# Alarm_system.net
KiCad netlist of a schematic drawn in Altium Designer
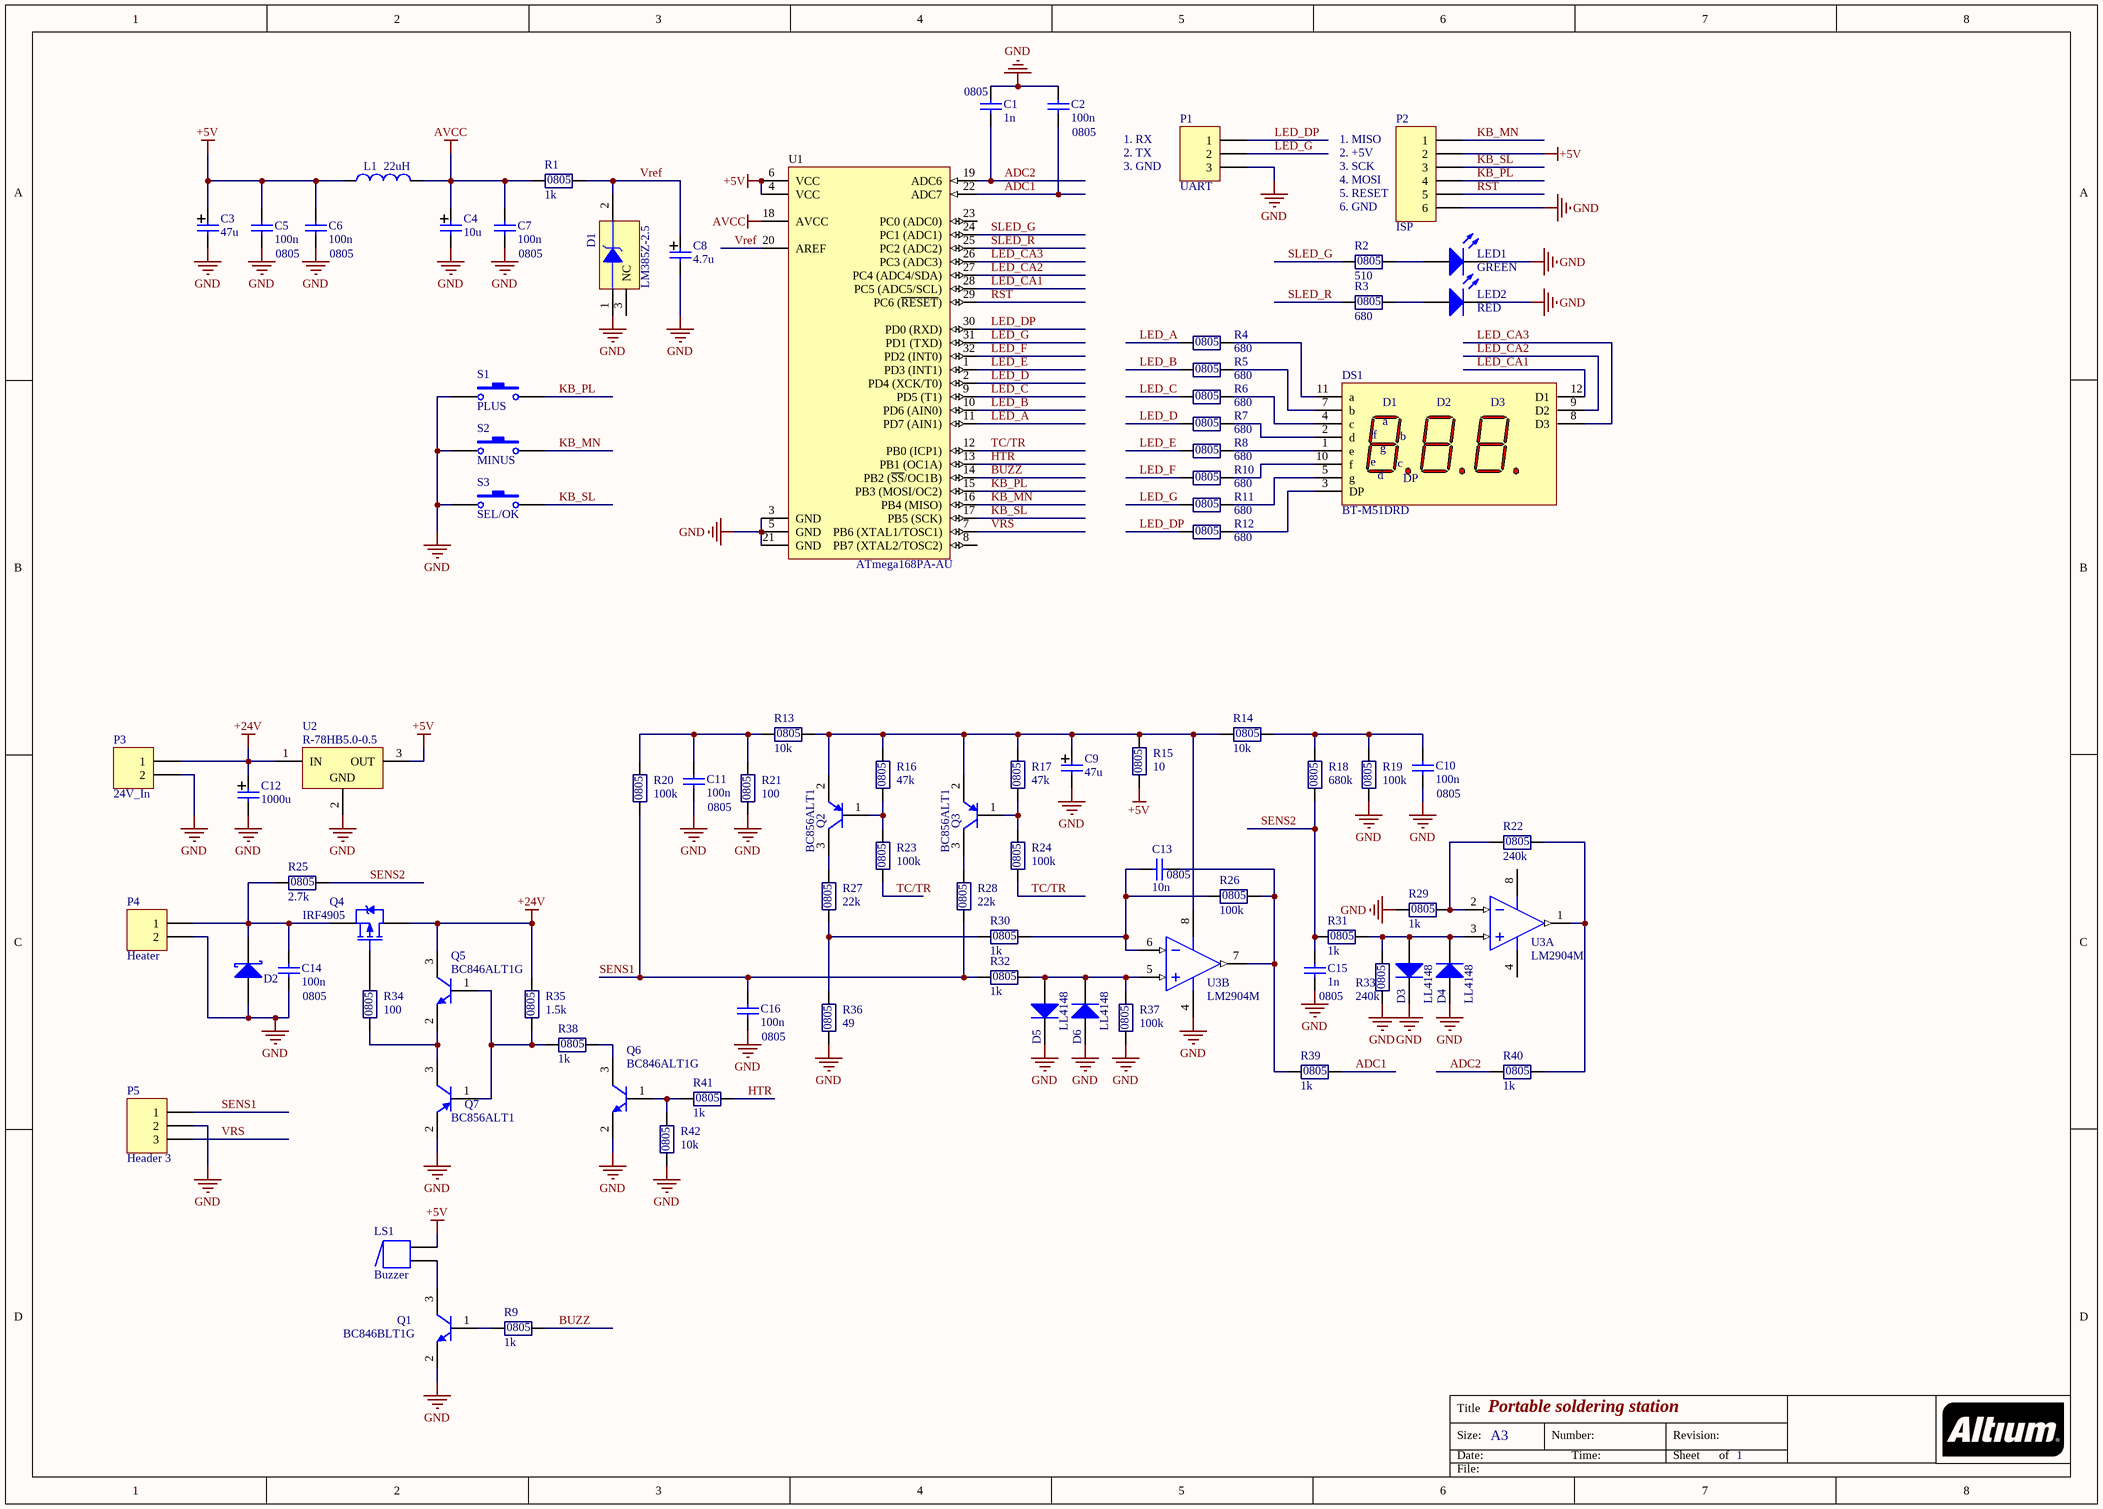
[diagram p0: Alarm system.SchDoc]

(export (version "E")
  (design (tool "Eeschema 10.0.6"))
  (components
    (comp (ref "C1")
      (value "0805")
      (footprint "CAPC2012X110N")
      (fields (field (name "ALTIUM_VALUE") "1n"))
      (libsource (lib "Passive components") (part "CAP"))
    )
    (comp (ref "C2")
      (value "0805")
      (footprint "CAPC2012X110N")
      (fields (field (name "ALTIUM_VALUE") "100n"))
      (libsource (lib "Passive components") (part "CAP"))
    )
    (comp (ref "C3")
      (value "47u")
      (footprint "CAPPR250-500X1100")
      (fields (field (name "Comment") "CAP_POL"))
      (libsource (lib "Passive components") (part "CAP_POL"))
    )
    (comp (ref "C4")
      (value "10u")
      (footprint "CAPPR250-500X1100")
      (fields (field (name "Comment") "CAP_POL"))
      (libsource (lib "Passive components") (part "CAP_POL"))
    )
    (comp (ref "C5")
      (value "0805")
      (footprint "CAPC2012X110N")
      (fields (field (name "ALTIUM_VALUE") "100n"))
      (libsource (lib "Passive components") (part "CAP"))
    )
    (comp (ref "C6")
      (value "0805")
      (footprint "CAPC2012X110N")
      (fields (field (name "ALTIUM_VALUE") "100n"))
      (libsource (lib "Passive components") (part "CAP"))
    )
    (comp (ref "C7")
      (value "0805")
      (footprint "CAPC2012X110N")
      (fields (field (name "ALTIUM_VALUE") "100n"))
      (libsource (lib "Passive components") (part "CAP"))
    )
    (comp (ref "C8")
      (value "4.7u")
      (footprint "CAPPR250-500X1100")
      (fields (field (name "Comment") "CAP_POL"))
      (libsource (lib "Passive components") (part "CAP_POL"))
    )
    (comp (ref "C9")
      (value "47u")
      (footprint "CAPPR250-500X1100")
      (fields (field (name "Comment") "CAP_POL"))
      (libsource (lib "Passive components") (part "CAP_POL"))
    )
    (comp (ref "C10")
      (value "0805")
      (footprint "CAPC2012X110N")
      (fields (field (name "ALTIUM_VALUE") "100n"))
      (libsource (lib "Passive components") (part "CAP"))
    )
    (comp (ref "C11")
      (value "0805")
      (footprint "CAPC2012X110N")
      (fields (field (name "ALTIUM_VALUE") "100n"))
      (libsource (lib "Passive components") (part "CAP"))
    )
    (comp (ref "C12")
      (value "1000u")
      (footprint "CAPPR500-1300X2150")
      (fields (field (name "Comment") "CAP_POL"))
      (libsource (lib "Passive components") (part "CAP_POL"))
    )
    (comp (ref "C13")
      (value "0805")
      (footprint "CAPC2012X110N")
      (fields (field (name "ALTIUM_VALUE") "10n"))
      (libsource (lib "Passive components") (part "CAP"))
    )
    (comp (ref "C14")
      (value "0805")
      (footprint "CAPC2012X110N")
      (fields (field (name "ALTIUM_VALUE") "100n"))
      (libsource (lib "Passive components") (part "CAP"))
    )
    (comp (ref "C15")
      (value "0805")
      (footprint "CAPC2012X110N")
      (fields (field (name "ALTIUM_VALUE") "1n"))
      (libsource (lib "Passive components") (part "CAP"))
    )
    (comp (ref "C16")
      (value "0805")
      (footprint "CAPC2012X110N")
      (fields (field (name "ALTIUM_VALUE") "100n"))
      (libsource (lib "Passive components") (part "CAP"))
    )
    (comp (ref "D1")
      (value "LM385Z-2.5")
      (footprint "TO-92AA-P127")
      (description "Micropower Voltage Reference Diode")
      (fields (field (name "PUBLISHER") "Altium Limited"))
      (libsource (lib "Motorola Power Mgt Voltage Reference") (part "LM385Z-2.5"))
    )
    (comp (ref "D2")
      (value "Schottky")
      (footprint "DO-41")
      (description "Schottky Rectifier")
      (libsource (lib "Diodes - Bridge Rectifiers") (part "Schottky"))
    )
    (comp (ref "D3")
      (value "LL4148")
      (footprint "SOD80")
      (description "Diode")
      (libsource (lib "Diodes - Bridge Rectifiers") (part "Diode"))
    )
    (comp (ref "D4")
      (value "LL4148")
      (footprint "SOD80")
      (description "Diode")
      (libsource (lib "Diodes - Bridge Rectifiers") (part "Diode"))
    )
    (comp (ref "D5")
      (value "LL4148")
      (footprint "SOD80")
      (description "Diode")
      (libsource (lib "Diodes - Bridge Rectifiers") (part "Diode"))
    )
    (comp (ref "D6")
      (value "LL4148")
      (footprint "SOD80")
      (description "Diode")
      (libsource (lib "Diodes - Bridge Rectifiers") (part "Diode"))
    )
    (comp (ref "DS1")
      (value "BT-M51DRD")
      (footprint "BT-M51DRD")
      (libsource (lib "Indicators") (part "Led_Ind_3_Digit"))
    )
    (comp (ref "L1")
      (value "22uH")
      (footprint "IND_BOURNS_PM43")
      (libsource (lib "ss3x7enc") (part "Drossel_AX"))
    )
    (comp (ref "LED1")
      (value "GREEN")
      (footprint "LED_3MM_GREEN_1C-2A")
      (description "Typical INFRARED GaAs LED")
      (fields (field (name "PUBLISHER") "Altium Limited"))
      (libsource (lib "Miscellaneous Devices") (part "LED0"))
    )
    (comp (ref "LED2")
      (value "RED")
      (footprint "LED_3MM_RED_1C-2A")
      (description "Typical INFRARED GaAs LED")
      (fields (field (name "PUBLISHER") "Altium Limited"))
      (libsource (lib "Miscellaneous Devices") (part "LED0"))
    )
    (comp (ref "LS1")
      (value "Buzzer")
      (footprint "buzzer")
      (description "Magnetic Transducer Buzzer")
      (fields (field (name "PUBLISHER") "Altium Limited"))
      (libsource (lib "Miscellaneous Devices") (part "Buzzer"))
    )
    (comp (ref "P1")
      (value "UART")
      (footprint "961103-6404-AR")
      (description "Header, 3-Pin")
      (fields (field (name "PUBLISHER") "Altium Limited"))
      (libsource (lib "Miscellaneous Connectors") (part "Header 3"))
    )
    (comp (ref "P2")
      (value "ISP")
      (footprint "961106-6404-AR")
      (description "Header, 6-Pin")
      (fields (field (name "PUBLISHER") "Altium Limited"))
      (libsource (lib "Miscellaneous Connectors") (part "Header 6"))
    )
    (comp (ref "P3")
      (value "24V_In")
      (footprint "PHOENIX_1715721")
      (description "Header, 2-Pin")
      (fields (field (name "PUBLISHER") "Altium Limited"))
      (libsource (lib "Miscellaneous Connectors") (part "Header 2"))
    )
    (comp (ref "P4")
      (value "Heater")
      (footprint "PHOENIX_1715721")
      (description "Header, 2-Pin")
      (fields (field (name "PUBLISHER") "Altium Limited"))
      (libsource (lib "Miscellaneous Connectors") (part "Header 2"))
    )
    (comp (ref "P5")
      (value "Header 3")
      (footprint "961103-6404-AR")
      (description "Header, 3-Pin")
      (fields (field (name "PUBLISHER") "Altium Limited"))
      (libsource (lib "Miscellaneous Connectors") (part "Header 3"))
    )
    (comp (ref "Q1")
      (value "BC846BLT1G")
      (footprint "SOT95P230X110-3N")
      (description "General Purpose Transistor, NPN Silicon, 3-Pin SOT-23, Pb-Free, Tape and Reel")
      (fields (field (name "MANUFACTURER") "On Semiconductor"))
      (libsource (lib "ON Semi General Purpose Transistors") (part "BC846BLT1G"))
    )
    (comp (ref "Q2")
      (value "BC856ALT1")
      (footprint "SOT95P230X110-3N")
      (description "General Purpose Transistor, PNP Silicon, 3-Pin SOT-23, Tape and Reel")
      (fields (field (name "MANUFACTURER") "On Semiconductor"))
      (libsource (lib "ON Semi General Purpose Transistors") (part "BC856ALT1"))
    )
    (comp (ref "Q3")
      (value "BC856ALT1")
      (footprint "SOT95P230X110-3N")
      (description "General Purpose Transistor, PNP Silicon, 3-Pin SOT-23, Tape and Reel")
      (fields (field (name "MANUFACTURER") "On Semiconductor"))
      (libsource (lib "ON Semi General Purpose Transistors") (part "BC856ALT1"))
    )
    (comp (ref "Q4")
      (value "IRF4905")
      (footprint "TO-220AB")
      (description "HEXFET Power MOSFET")
      (fields (field (name "PUBLISHER") "Altium Limited"))
      (libsource (lib "IR Discrete MOSFET - Power") (part "IRF4905"))
    )
    (comp (ref "Q5")
      (value "BC846ALT1G")
      (footprint "SOT95P230X110-3N")
      (description "General Purpose Transistor, NPN Silicon, 3-Pin SOT-23, Pb-Free, Tape and Reel")
      (fields (field (name "MANUFACTURER") "On Semiconductor"))
      (libsource (lib "ON Semi General Purpose Transistors") (part "BC846ALT1G"))
    )
    (comp (ref "Q6")
      (value "BC846ALT1G")
      (footprint "SOT95P230X110-3N")
      (description "General Purpose Transistor, NPN Silicon, 3-Pin SOT-23, Pb-Free, Tape and Reel")
      (fields (field (name "MANUFACTURER") "On Semiconductor"))
      (libsource (lib "ON Semi General Purpose Transistors") (part "BC846ALT1G"))
    )
    (comp (ref "Q7")
      (value "BC856ALT1")
      (footprint "SOT95P230X110-3N")
      (description "General Purpose Transistor, PNP Silicon, 3-Pin SOT-23, Tape and Reel")
      (fields (field (name "MANUFACTURER") "On Semiconductor"))
      (libsource (lib "ON Semi General Purpose Transistors") (part "BC856ALT1"))
    )
    (comp (ref "R1")
      (value "0805")
      (footprint "RESC2012X50N")
      (fields (field (name "ALTIUM_VALUE") "1k"))
      (libsource (lib "Passive components") (part "Resistor"))
    )
    (comp (ref "R2")
      (value "0805")
      (footprint "RESC2012X50N")
      (fields (field (name "ALTIUM_VALUE") "510"))
      (libsource (lib "Passive components") (part "Resistor"))
    )
    (comp (ref "R3")
      (value "0805")
      (footprint "RESC2012X50N")
      (fields (field (name "ALTIUM_VALUE") "680"))
      (libsource (lib "Passive components") (part "Resistor"))
    )
    (comp (ref "R4")
      (value "0805")
      (footprint "RESC2012X50N")
      (fields (field (name "ALTIUM_VALUE") "680"))
      (libsource (lib "Passive components") (part "Resistor"))
    )
    (comp (ref "R5")
      (value "0805")
      (footprint "RESC2012X50N")
      (fields (field (name "ALTIUM_VALUE") "680"))
      (libsource (lib "Passive components") (part "Resistor"))
    )
    (comp (ref "R6")
      (value "0805")
      (footprint "RESC2012X50N")
      (fields (field (name "ALTIUM_VALUE") "680"))
      (libsource (lib "Passive components") (part "Resistor"))
    )
    (comp (ref "R7")
      (value "0805")
      (footprint "RESC2012X50N")
      (fields (field (name "ALTIUM_VALUE") "680"))
      (libsource (lib "Passive components") (part "Resistor"))
    )
    (comp (ref "R8")
      (value "0805")
      (footprint "RESC2012X50N")
      (fields (field (name "ALTIUM_VALUE") "680"))
      (libsource (lib "Passive components") (part "Resistor"))
    )
    (comp (ref "R9")
      (value "0805")
      (footprint "RESC2012X50N")
      (fields (field (name "ALTIUM_VALUE") "1k"))
      (libsource (lib "Passive components") (part "Resistor"))
    )
    (comp (ref "R10")
      (value "0805")
      (footprint "RESC2012X50N")
      (fields (field (name "ALTIUM_VALUE") "680"))
      (libsource (lib "Passive components") (part "Resistor"))
    )
    (comp (ref "R11")
      (value "0805")
      (footprint "RESC2012X50N")
      (fields (field (name "ALTIUM_VALUE") "680"))
      (libsource (lib "Passive components") (part "Resistor"))
    )
    (comp (ref "R12")
      (value "0805")
      (footprint "RESC2012X50N")
      (fields (field (name "ALTIUM_VALUE") "680"))
      (libsource (lib "Passive components") (part "Resistor"))
    )
    (comp (ref "R13")
      (value "0805")
      (footprint "RESC2012X50N")
      (fields (field (name "ALTIUM_VALUE") "10k"))
      (libsource (lib "Passive components") (part "Resistor"))
    )
    (comp (ref "R14")
      (value "0805")
      (footprint "RESC2012X50N")
      (fields (field (name "ALTIUM_VALUE") "10k"))
      (libsource (lib "Passive components") (part "Resistor"))
    )
    (comp (ref "R15")
      (value "0805")
      (footprint "RESC2012X50N")
      (fields (field (name "ALTIUM_VALUE") "10"))
      (libsource (lib "Passive components") (part "Resistor"))
    )
    (comp (ref "R16")
      (value "0805")
      (footprint "RESC2012X50N")
      (fields (field (name "ALTIUM_VALUE") "47k"))
      (libsource (lib "Passive components") (part "Resistor"))
    )
    (comp (ref "R17")
      (value "0805")
      (footprint "RESC2012X50N")
      (fields (field (name "ALTIUM_VALUE") "47k"))
      (libsource (lib "Passive components") (part "Resistor"))
    )
    (comp (ref "R18")
      (value "0805")
      (footprint "RESC2012X50N")
      (fields (field (name "ALTIUM_VALUE") "680k"))
      (libsource (lib "Passive components") (part "Resistor"))
    )
    (comp (ref "R19")
      (value "0805")
      (footprint "RESC2012X50N")
      (fields (field (name "ALTIUM_VALUE") "100k"))
      (libsource (lib "Passive components") (part "Resistor"))
    )
    (comp (ref "R20")
      (value "0805")
      (footprint "RESC2012X50N")
      (fields (field (name "ALTIUM_VALUE") "100k"))
      (libsource (lib "Passive components") (part "Resistor"))
    )
    (comp (ref "R21")
      (value "0805")
      (footprint "RESC2012X50N")
      (fields (field (name "ALTIUM_VALUE") "100"))
      (libsource (lib "Passive components") (part "Resistor"))
    )
    (comp (ref "R22")
      (value "0805")
      (footprint "RESC2012X50N")
      (fields (field (name "ALTIUM_VALUE") "240k"))
      (libsource (lib "Passive components") (part "Resistor"))
    )
    (comp (ref "R23")
      (value "0805")
      (footprint "RESC2012X50N")
      (fields (field (name "ALTIUM_VALUE") "100k"))
      (libsource (lib "Passive components") (part "Resistor"))
    )
    (comp (ref "R24")
      (value "0805")
      (footprint "RESC2012X50N")
      (fields (field (name "ALTIUM_VALUE") "100k"))
      (libsource (lib "Passive components") (part "Resistor"))
    )
    (comp (ref "R25")
      (value "0805")
      (footprint "RESC2012X50N")
      (fields (field (name "ALTIUM_VALUE") "2.7k"))
      (libsource (lib "Passive components") (part "Resistor"))
    )
    (comp (ref "R26")
      (value "0805")
      (footprint "RESC2012X50N")
      (fields (field (name "ALTIUM_VALUE") "100k"))
      (libsource (lib "Passive components") (part "Resistor"))
    )
    (comp (ref "R27")
      (value "0805")
      (footprint "RESC2012X50N")
      (fields (field (name "ALTIUM_VALUE") "22k"))
      (libsource (lib "Passive components") (part "Resistor"))
    )
    (comp (ref "R28")
      (value "0805")
      (footprint "RESC2012X50N")
      (fields (field (name "ALTIUM_VALUE") "22k"))
      (libsource (lib "Passive components") (part "Resistor"))
    )
    (comp (ref "R29")
      (value "0805")
      (footprint "RESC2012X50N")
      (fields (field (name "ALTIUM_VALUE") "1k"))
      (libsource (lib "Passive components") (part "Resistor"))
    )
    (comp (ref "R30")
      (value "0805")
      (footprint "RESC2012X50N")
      (fields (field (name "ALTIUM_VALUE") "1k"))
      (libsource (lib "Passive components") (part "Resistor"))
    )
    (comp (ref "R31")
      (value "0805")
      (footprint "RESC2012X50N")
      (fields (field (name "ALTIUM_VALUE") "1k"))
      (libsource (lib "Passive components") (part "Resistor"))
    )
    (comp (ref "R32")
      (value "0805")
      (footprint "RESC2012X50N")
      (fields (field (name "ALTIUM_VALUE") "1k"))
      (libsource (lib "Passive components") (part "Resistor"))
    )
    (comp (ref "R33")
      (value "0805")
      (footprint "RESC2012X50N")
      (fields (field (name "ALTIUM_VALUE") "240k"))
      (libsource (lib "Passive components") (part "Resistor"))
    )
    (comp (ref "R34")
      (value "0805")
      (footprint "RESC2012X50N")
      (fields (field (name "ALTIUM_VALUE") "100"))
      (libsource (lib "Passive components") (part "Resistor"))
    )
    (comp (ref "R35")
      (value "0805")
      (footprint "RESC2012X50N")
      (fields (field (name "ALTIUM_VALUE") "1.5k"))
      (libsource (lib "Passive components") (part "Resistor"))
    )
    (comp (ref "R36")
      (value "0805")
      (footprint "RESC2012X50N")
      (fields (field (name "ALTIUM_VALUE") "49"))
      (libsource (lib "Passive components") (part "Resistor"))
    )
    (comp (ref "R37")
      (value "0805")
      (footprint "RESC2012X50N")
      (fields (field (name "ALTIUM_VALUE") "100k"))
      (libsource (lib "Passive components") (part "Resistor"))
    )
    (comp (ref "R38")
      (value "0805")
      (footprint "RESC2012X50N")
      (fields (field (name "ALTIUM_VALUE") "1k"))
      (libsource (lib "Passive components") (part "Resistor"))
    )
    (comp (ref "R39")
      (value "0805")
      (footprint "RESC2012X50N")
      (fields (field (name "ALTIUM_VALUE") "1k"))
      (libsource (lib "Passive components") (part "Resistor"))
    )
    (comp (ref "R40")
      (value "0805")
      (footprint "RESC2012X50N")
      (fields (field (name "ALTIUM_VALUE") "1k"))
      (libsource (lib "Passive components") (part "Resistor"))
    )
    (comp (ref "R41")
      (value "0805")
      (footprint "RESC2012X50N")
      (fields (field (name "ALTIUM_VALUE") "1k"))
      (libsource (lib "Passive components") (part "Resistor"))
    )
    (comp (ref "R42")
      (value "0805")
      (footprint "RESC2012X50N")
      (fields (field (name "ALTIUM_VALUE") "10k"))
      (libsource (lib "Passive components") (part "Resistor"))
    )
    (comp (ref "S1")
      (value "PLUS")
      (footprint "PB_OMRON_B3F-1070")
      (description "Switch")
      (fields (field (name "PUBLISHER") "Altium Limited"))
      (libsource (lib "Miscellaneous Devices") (part "SW-PB"))
    )
    (comp (ref "S2")
      (value "MINUS")
      (footprint "PB_OMRON_B3F-1070")
      (description "Switch")
      (fields (field (name "PUBLISHER") "Altium Limited"))
      (libsource (lib "Miscellaneous Devices") (part "SW-PB"))
    )
    (comp (ref "S3")
      (value "SEL/OK")
      (footprint "PB_OMRON_B3F-1070")
      (description "Switch")
      (fields (field (name "PUBLISHER") "Altium Limited"))
      (libsource (lib "Miscellaneous Devices") (part "SW-PB"))
    )
    (comp (ref "U1")
      (value "ATmega168PA-AU")
      (footprint "32A_N")
      (fields (field (name "PUBLISHER") "Altium Limited"))
      (libsource (lib "Atmel Microcontroller 8-Bit megaAVR") (part "ATmega8A-AU"))
    )
    (comp (ref "U2")
      (value "R-78HB5.0-0.5")
      (footprint "SIP-3")
      (description "3-Terminal Positive Fixed Voltage Regulator")
      (fields (field (name "MANUFACTURER PART NUMBER") "R-78E5.0-1.0"))
      (libsource (lib "Motorola Power Mgt Voltage Regulator") (part "MC7805ACT"))
    )
    (comp (ref "U3")
      (value "LM2904M")
      (footprint "M08A_N")
      (description "Low Power Dual Operational Amplifier, 8-pin Narrow SOIC")
      (fields
        (field (name "MANUFACTURER") "National Semiconductor")
        (field (name "PUBLISHER") "Altium Limited")
      )
      (libsource (lib "NSC Amplifier") (part "LM2904M"))
    )
  )
  (nets
    (net (code "1") (name "+5V") (class "Default")
      (node (ref "C3") (pin "1") (pinfunction "1_1") (pintype "passive"))
      (node (ref "C5") (pin "2") (pinfunction "2_2") (pintype "passive"))
      (node (ref "C6") (pin "2") (pinfunction "2_2") (pintype "passive"))
      (node (ref "L1") (pin "2") (pinfunction "2_2") (pintype "passive"))
      (node (ref "LS1") (pin "1") (pinfunction "1_1") (pintype "passive"))
      (node (ref "P2") (pin "2") (pinfunction "2_2") (pintype "passive"))
      (node (ref "R15") (pin "1") (pinfunction "1_1") (pintype "passive"))
      (node (ref "U1") (pin "4") (pinfunction "VCC_4") (pintype "power_in"))
      (node (ref "U1") (pin "6") (pinfunction "VCC_6") (pintype "power_in"))
      (node (ref "U2") (pin "3") (pinfunction "OUT_3") (pintype "power_in"))
    )
    (net (code "2") (name "+24V") (class "Default")
      (node (ref "C12") (pin "1") (pinfunction "1_1") (pintype "passive"))
      (node (ref "P3") (pin "1") (pinfunction "1_1") (pintype "passive"))
      (node (ref "Q4") (pin "2") (pinfunction "D_2") (pintype "passive"))
      (node (ref "Q5") (pin "3") (pinfunction "C_3") (pintype "passive"))
      (node (ref "R35") (pin "2") (pinfunction "2_2") (pintype "passive"))
      (node (ref "U2") (pin "1") (pinfunction "IN_1") (pintype "power_in"))
    )
    (net (code "3") (name "/ADC1") (class "Default")
      (node (ref "C2") (pin "2") (pinfunction "2_2") (pintype "passive"))
      (node (ref "R39") (pin "2") (pinfunction "2_2") (pintype "passive"))
      (node (ref "U1") (pin "22") (pinfunction "ADC7_22") (pintype "input"))
    )
    (net (code "4") (name "/ADC2") (class "Default")
      (node (ref "C1") (pin "2") (pinfunction "2_2") (pintype "passive"))
      (node (ref "R40") (pin "1") (pinfunction "1_1") (pintype "passive"))
      (node (ref "U1") (pin "19") (pinfunction "ADC6_19") (pintype "input"))
    )
    (net (code "5") (name "/BUZZ") (class "Default")
      (node (ref "R9") (pin "2") (pinfunction "2_2") (pintype "passive"))
      (node (ref "U1") (pin "14") (pinfunction "PB2_(~{SS}/OC1B)_14") (pintype "bidirectional"))
    )
    (net (code "6") (name "/HTR") (class "Default")
      (node (ref "R41") (pin "2") (pinfunction "2_2") (pintype "passive"))
      (node (ref "U1") (pin "13") (pinfunction "PB1_(OC1A)_13") (pintype "bidirectional"))
    )
    (net (code "7") (name "/KB_MN") (class "Default")
      (node (ref "P2") (pin "1") (pinfunction "1_1") (pintype "passive"))
      (node (ref "S2") (pin "2") (pinfunction "2_2") (pintype "passive"))
      (node (ref "U1") (pin "16") (pinfunction "PB4_(MISO)_16") (pintype "bidirectional"))
    )
    (net (code "8") (name "/KB_PL") (class "Default")
      (node (ref "P2") (pin "4") (pinfunction "4_4") (pintype "passive"))
      (node (ref "S1") (pin "2") (pinfunction "2_2") (pintype "passive"))
      (node (ref "U1") (pin "15") (pinfunction "PB3_(MOSI/OC2)_15") (pintype "bidirectional"))
    )
    (net (code "9") (name "/KB_SL") (class "Default")
      (node (ref "P2") (pin "3") (pinfunction "3_3") (pintype "passive"))
      (node (ref "S3") (pin "2") (pinfunction "2_2") (pintype "passive"))
      (node (ref "U1") (pin "17") (pinfunction "PB5_(SCK)_17") (pintype "bidirectional"))
    )
    (net (code "10") (name "/LED_A") (class "Default")
      (node (ref "R4") (pin "1") (pinfunction "1_1") (pintype "passive"))
      (node (ref "U1") (pin "11") (pinfunction "PD7_(AIN1)_11") (pintype "bidirectional"))
    )
    (net (code "11") (name "/LED_B") (class "Default")
      (node (ref "R5") (pin "1") (pinfunction "1_1") (pintype "passive"))
      (node (ref "U1") (pin "10") (pinfunction "PD6_(AIN0)_10") (pintype "bidirectional"))
    )
    (net (code "12") (name "/LED_C") (class "Default")
      (node (ref "R6") (pin "1") (pinfunction "1_1") (pintype "passive"))
      (node (ref "U1") (pin "9") (pinfunction "PD5_(T1)_9") (pintype "bidirectional"))
    )
    (net (code "13") (name "/LED_CA1") (class "Default")
      (node (ref "DS1") (pin "12") (pinfunction "D1_12") (pintype "passive"))
      (node (ref "U1") (pin "28") (pinfunction "PC5_(ADC5/SCL)_28") (pintype "bidirectional"))
    )
    (net (code "14") (name "/LED_CA2") (class "Default")
      (node (ref "DS1") (pin "9") (pinfunction "D2_9") (pintype "passive"))
      (node (ref "U1") (pin "27") (pinfunction "PC4_(ADC4/SDA)_27") (pintype "bidirectional"))
    )
    (net (code "15") (name "/LED_CA3") (class "Default")
      (node (ref "DS1") (pin "8") (pinfunction "D3_8") (pintype "passive"))
      (node (ref "U1") (pin "26") (pinfunction "PC3_(ADC3)_26") (pintype "bidirectional"))
    )
    (net (code "16") (name "/LED_D") (class "Default")
      (node (ref "R7") (pin "1") (pinfunction "1_1") (pintype "passive"))
      (node (ref "U1") (pin "2") (pinfunction "PD4_(XCK/T0)_2") (pintype "bidirectional"))
    )
    (net (code "17") (name "/LED_DP") (class "Default")
      (node (ref "P1") (pin "1") (pinfunction "1_1") (pintype "passive"))
      (node (ref "R12") (pin "1") (pinfunction "1_1") (pintype "passive"))
      (node (ref "U1") (pin "30") (pinfunction "PD0_(RXD)_30") (pintype "bidirectional"))
    )
    (net (code "18") (name "/LED_E") (class "Default")
      (node (ref "R8") (pin "1") (pinfunction "1_1") (pintype "passive"))
      (node (ref "U1") (pin "1") (pinfunction "PD3_(INT1)_1") (pintype "bidirectional"))
    )
    (net (code "19") (name "/LED_F") (class "Default")
      (node (ref "R10") (pin "1") (pinfunction "1_1") (pintype "passive"))
      (node (ref "U1") (pin "32") (pinfunction "PD2_(INT0)_32") (pintype "bidirectional"))
    )
    (net (code "20") (name "/LED_G") (class "Default")
      (node (ref "P1") (pin "2") (pinfunction "2_2") (pintype "passive"))
      (node (ref "R11") (pin "1") (pinfunction "1_1") (pintype "passive"))
      (node (ref "U1") (pin "31") (pinfunction "PD1_(TXD)_31") (pintype "bidirectional"))
    )
    (net (code "21") (name "/RST") (class "Default")
      (node (ref "P2") (pin "5") (pinfunction "5_5") (pintype "passive"))
      (node (ref "U1") (pin "29") (pinfunction "PC6_(~{RESET})_29") (pintype "bidirectional"))
    )
    (net (code "22") (name "/SENS1") (class "Default")
      (node (ref "C16") (pin "2") (pinfunction "2_2") (pintype "passive"))
      (node (ref "P5") (pin "1") (pinfunction "1_1") (pintype "passive"))
      (node (ref "R20") (pin "1") (pinfunction "1_1") (pintype "passive"))
      (node (ref "R28") (pin "1") (pinfunction "1_1") (pintype "passive"))
      (node (ref "R32") (pin "1") (pinfunction "1_1") (pintype "passive"))
    )
    (net (code "23") (name "/SENS2") (class "Default")
      (node (ref "C15") (pin "2") (pinfunction "2_2") (pintype "passive"))
      (node (ref "R18") (pin "1") (pinfunction "1_1") (pintype "passive"))
      (node (ref "R25") (pin "2") (pinfunction "2_2") (pintype "passive"))
      (node (ref "R31") (pin "1") (pinfunction "1_1") (pintype "passive"))
    )
    (net (code "24") (name "/SLED_G") (class "Default")
      (node (ref "R2") (pin "1") (pinfunction "1_1") (pintype "passive"))
      (node (ref "U1") (pin "24") (pinfunction "PC1_(ADC1)_24") (pintype "bidirectional"))
    )
    (net (code "25") (name "/SLED_R") (class "Default")
      (node (ref "R3") (pin "1") (pinfunction "1_1") (pintype "passive"))
      (node (ref "U1") (pin "25") (pinfunction "PC2_(ADC2)_25") (pintype "bidirectional"))
    )
    (net (code "26") (name "/TC{slash}TR") (class "Default")
      (node (ref "R23") (pin "1") (pinfunction "1_1") (pintype "passive"))
      (node (ref "R24") (pin "1") (pinfunction "1_1") (pintype "passive"))
      (node (ref "U1") (pin "12") (pinfunction "PB0_(ICP1)_12") (pintype "bidirectional"))
    )
    (net (code "27") (name "/VRS") (class "Default")
      (node (ref "P5") (pin "3") (pinfunction "3_3") (pintype "passive"))
      (node (ref "U1") (pin "7") (pinfunction "PB6_(XTAL1/TOSC1)_7") (pintype "bidirectional"))
    )
    (net (code "28") (name "/Vref") (class "Default")
      (node (ref "C8") (pin "1") (pinfunction "1_1") (pintype "passive"))
      (node (ref "D1") (pin "2") (pinfunction "K_2") (pintype "passive"))
      (node (ref "R1") (pin "2") (pinfunction "2_2") (pintype "passive"))
      (node (ref "U1") (pin "20") (pinfunction "AREF_20") (pintype "power_in"))
    )
    (net (code "29") (name "AVCC") (class "Default")
      (node (ref "C4") (pin "1") (pinfunction "1_1") (pintype "passive"))
      (node (ref "C7") (pin "2") (pinfunction "2_2") (pintype "passive"))
      (node (ref "L1") (pin "1") (pinfunction "1_1") (pintype "passive"))
      (node (ref "R1") (pin "1") (pinfunction "1_1") (pintype "passive"))
      (node (ref "U1") (pin "18") (pinfunction "AVCC_18") (pintype "power_in"))
    )
    (net (code "30") (name "GND") (class "Default")
      (node (ref "C1") (pin "1") (pinfunction "1_1") (pintype "passive"))
      (node (ref "C10") (pin "1") (pinfunction "1_1") (pintype "passive"))
      (node (ref "C11") (pin "1") (pinfunction "1_1") (pintype "passive"))
      (node (ref "C12") (pin "2") (pinfunction "2_2") (pintype "passive"))
      (node (ref "C14") (pin "1") (pinfunction "1_1") (pintype "passive"))
      (node (ref "C15") (pin "1") (pinfunction "1_1") (pintype "passive"))
      (node (ref "C16") (pin "1") (pinfunction "1_1") (pintype "passive"))
      (node (ref "C2") (pin "1") (pinfunction "1_1") (pintype "passive"))
      (node (ref "C3") (pin "2") (pinfunction "2_2") (pintype "passive"))
      (node (ref "C4") (pin "2") (pinfunction "2_2") (pintype "passive"))
      (node (ref "C5") (pin "1") (pinfunction "1_1") (pintype "passive"))
      (node (ref "C6") (pin "1") (pinfunction "1_1") (pintype "passive"))
      (node (ref "C7") (pin "1") (pinfunction "1_1") (pintype "passive"))
      (node (ref "C8") (pin "2") (pinfunction "2_2") (pintype "passive"))
      (node (ref "C9") (pin "2") (pinfunction "2_2") (pintype "passive"))
      (node (ref "D1") (pin "1") (pinfunction "A_1") (pintype "passive"))
      (node (ref "D2") (pin "1") (pinfunction "A_1") (pintype "passive"))
      (node (ref "D3") (pin "2") (pinfunction "K_2") (pintype "passive"))
      (node (ref "D4") (pin "1") (pinfunction "A_1") (pintype "passive"))
      (node (ref "D5") (pin "2") (pinfunction "K_2") (pintype "passive"))
      (node (ref "D6") (pin "1") (pinfunction "A_1") (pintype "passive"))
      (node (ref "LED1") (pin "2") (pinfunction "K_2") (pintype "passive"))
      (node (ref "LED2") (pin "2") (pinfunction "K_2") (pintype "passive"))
      (node (ref "P1") (pin "3") (pinfunction "3_3") (pintype "passive"))
      (node (ref "P2") (pin "6") (pinfunction "6_6") (pintype "passive"))
      (node (ref "P3") (pin "2") (pinfunction "2_2") (pintype "passive"))
      (node (ref "P4") (pin "2") (pinfunction "2_2") (pintype "passive"))
      (node (ref "P5") (pin "2") (pinfunction "2_2") (pintype "passive"))
      (node (ref "Q1") (pin "2") (pinfunction "E_2") (pintype "passive"))
      (node (ref "Q6") (pin "2") (pinfunction "E_2") (pintype "passive"))
      (node (ref "Q7") (pin "2") (pinfunction "E_2") (pintype "passive"))
      (node (ref "R19") (pin "1") (pinfunction "1_1") (pintype "passive"))
      (node (ref "R21") (pin "1") (pinfunction "1_1") (pintype "passive"))
      (node (ref "R29") (pin "1") (pinfunction "1_1") (pintype "passive"))
      (node (ref "R33") (pin "1") (pinfunction "1_1") (pintype "passive"))
      (node (ref "R36") (pin "1") (pinfunction "1_1") (pintype "passive"))
      (node (ref "R37") (pin "1") (pinfunction "1_1") (pintype "passive"))
      (node (ref "R42") (pin "1") (pinfunction "1_1") (pintype "passive"))
      (node (ref "S1") (pin "1") (pinfunction "1_1") (pintype "passive"))
      (node (ref "S2") (pin "1") (pinfunction "1_1") (pintype "passive"))
      (node (ref "S3") (pin "1") (pinfunction "1_1") (pintype "passive"))
      (node (ref "U1") (pin "21") (pinfunction "GND_21") (pintype "power_in"))
      (node (ref "U1") (pin "3") (pinfunction "GND_3") (pintype "power_in"))
      (node (ref "U1") (pin "5") (pinfunction "GND_5") (pintype "power_in"))
      (node (ref "U2") (pin "2") (pinfunction "GND_2") (pintype "power_in"))
      (node (ref "U3") (pin "4") (pinfunction "GND_4") (pintype "power_in"))
    )
    (net (code "31") (name "Net-(C10-Pad2)") (class "Default")
      (node (ref "C10") (pin "2") (pinfunction "2_2") (pintype "passive"))
      (node (ref "R14") (pin "2") (pinfunction "2_2") (pintype "passive"))
      (node (ref "R18") (pin "2") (pinfunction "2_2") (pintype "passive"))
      (node (ref "R19") (pin "2") (pinfunction "2_2") (pintype "passive"))
    )
    (net (code "32") (name "Net-(C11-Pad2)") (class "Default")
      (node (ref "C11") (pin "2") (pinfunction "2_2") (pintype "passive"))
      (node (ref "R13") (pin "1") (pinfunction "1_1") (pintype "passive"))
      (node (ref "R20") (pin "2") (pinfunction "2_2") (pintype "passive"))
      (node (ref "R21") (pin "2") (pinfunction "2_2") (pintype "passive"))
    )
    (net (code "33") (name "Net-(D2-K)") (class "Default")
      (node (ref "C14") (pin "2") (pinfunction "2_2") (pintype "passive"))
      (node (ref "D2") (pin "2") (pinfunction "K_2") (pintype "passive"))
      (node (ref "P4") (pin "1") (pinfunction "1_1") (pintype "passive"))
      (node (ref "Q4") (pin "3") (pinfunction "S_3") (pintype "passive"))
      (node (ref "R25") (pin "1") (pinfunction "1_1") (pintype "passive"))
    )
    (net (code "34") (name "Net-(D3-A)") (class "Default")
      (node (ref "D3") (pin "1") (pinfunction "A_1") (pintype "passive"))
      (node (ref "D4") (pin "2") (pinfunction "K_2") (pintype "passive"))
      (node (ref "R31") (pin "2") (pinfunction "2_2") (pintype "passive"))
      (node (ref "R33") (pin "2") (pinfunction "2_2") (pintype "passive"))
      (node (ref "U3") (pin "3") (pinfunction "INA+_3") (pintype "input"))
    )
    (net (code "35") (name "Net-(D5-A)") (class "Default")
      (node (ref "D5") (pin "1") (pinfunction "A_1") (pintype "passive"))
      (node (ref "D6") (pin "2") (pinfunction "K_2") (pintype "passive"))
      (node (ref "R32") (pin "2") (pinfunction "2_2") (pintype "passive"))
      (node (ref "R37") (pin "2") (pinfunction "2_2") (pintype "passive"))
      (node (ref "U3") (pin "5") (pinfunction "INB+_5") (pintype "input"))
    )
    (net (code "36") (name "Net-(DS1-DP)") (class "Default")
      (node (ref "DS1") (pin "3") (pinfunction "DP_3") (pintype "passive"))
      (node (ref "R12") (pin "2") (pinfunction "2_2") (pintype "passive"))
    )
    (net (code "37") (name "Net-(DS1-a)") (class "Default")
      (node (ref "DS1") (pin "11") (pinfunction "a_11") (pintype "passive"))
      (node (ref "R4") (pin "2") (pinfunction "2_2") (pintype "passive"))
    )
    (net (code "38") (name "Net-(DS1-b)") (class "Default")
      (node (ref "DS1") (pin "7") (pinfunction "b_7") (pintype "passive"))
      (node (ref "R5") (pin "2") (pinfunction "2_2") (pintype "passive"))
    )
    (net (code "39") (name "Net-(DS1-c)") (class "Default")
      (node (ref "DS1") (pin "4") (pinfunction "c_4") (pintype "passive"))
      (node (ref "R6") (pin "2") (pinfunction "2_2") (pintype "passive"))
    )
    (net (code "40") (name "Net-(DS1-d)") (class "Default")
      (node (ref "DS1") (pin "2") (pinfunction "d_2") (pintype "passive"))
      (node (ref "R7") (pin "2") (pinfunction "2_2") (pintype "passive"))
    )
    (net (code "41") (name "Net-(DS1-e)") (class "Default")
      (node (ref "DS1") (pin "1") (pinfunction "e_1") (pintype "passive"))
      (node (ref "R8") (pin "2") (pinfunction "2_2") (pintype "passive"))
    )
    (net (code "42") (name "Net-(DS1-f)") (class "Default")
      (node (ref "DS1") (pin "10") (pinfunction "f_10") (pintype "passive"))
      (node (ref "R10") (pin "2") (pinfunction "2_2") (pintype "passive"))
    )
    (net (code "43") (name "Net-(DS1-g)") (class "Default")
      (node (ref "DS1") (pin "5") (pinfunction "g_5") (pintype "passive"))
      (node (ref "R11") (pin "2") (pinfunction "2_2") (pintype "passive"))
    )
    (net (code "44") (name "Net-(LED1-A)") (class "Default")
      (node (ref "LED1") (pin "1") (pinfunction "A_1") (pintype "passive"))
      (node (ref "R2") (pin "2") (pinfunction "2_2") (pintype "passive"))
    )
    (net (code "45") (name "Net-(LED2-A)") (class "Default")
      (node (ref "LED2") (pin "1") (pinfunction "A_1") (pintype "passive"))
      (node (ref "R3") (pin "2") (pinfunction "2_2") (pintype "passive"))
    )
    (net (code "46") (name "Net-(Q1-B)") (class "Default")
      (node (ref "Q1") (pin "1") (pinfunction "B_1") (pintype "passive"))
      (node (ref "R9") (pin "1") (pinfunction "1_1") (pintype "passive"))
    )
    (net (code "47") (name "Net-(Q1-C)") (class "Default")
      (node (ref "LS1") (pin "2") (pinfunction "2_2") (pintype "passive"))
      (node (ref "Q1") (pin "3") (pinfunction "C_3") (pintype "passive"))
    )
    (net (code "48") (name "Net-(Q2-B)") (class "Default")
      (node (ref "Q2") (pin "1") (pinfunction "B_1") (pintype "passive"))
      (node (ref "R16") (pin "1") (pinfunction "1_1") (pintype "passive"))
      (node (ref "R23") (pin "2") (pinfunction "2_2") (pintype "passive"))
    )
    (net (code "49") (name "Net-(Q2-C)") (class "Default")
      (node (ref "Q2") (pin "3") (pinfunction "C_3") (pintype "passive"))
      (node (ref "R27") (pin "2") (pinfunction "2_2") (pintype "passive"))
    )
    (net (code "50") (name "Net-(Q2-E)") (class "Default")
      (node (ref "C9") (pin "1") (pinfunction "1_1") (pintype "passive"))
      (node (ref "Q2") (pin "2") (pinfunction "E_2") (pintype "passive"))
      (node (ref "Q3") (pin "2") (pinfunction "E_2") (pintype "passive"))
      (node (ref "R13") (pin "2") (pinfunction "2_2") (pintype "passive"))
      (node (ref "R14") (pin "1") (pinfunction "1_1") (pintype "passive"))
      (node (ref "R15") (pin "2") (pinfunction "2_2") (pintype "passive"))
      (node (ref "R16") (pin "2") (pinfunction "2_2") (pintype "passive"))
      (node (ref "R17") (pin "2") (pinfunction "2_2") (pintype "passive"))
      (node (ref "U3") (pin "8") (pinfunction "V+_8") (pintype "power_in"))
    )
    (net (code "51") (name "Net-(Q3-B)") (class "Default")
      (node (ref "Q3") (pin "1") (pinfunction "B_1") (pintype "passive"))
      (node (ref "R17") (pin "1") (pinfunction "1_1") (pintype "passive"))
      (node (ref "R24") (pin "2") (pinfunction "2_2") (pintype "passive"))
    )
    (net (code "52") (name "Net-(Q3-C)") (class "Default")
      (node (ref "Q3") (pin "3") (pinfunction "C_3") (pintype "passive"))
      (node (ref "R28") (pin "2") (pinfunction "2_2") (pintype "passive"))
    )
    (net (code "53") (name "Net-(Q4-G)") (class "Default")
      (node (ref "Q4") (pin "1") (pinfunction "G_1") (pintype "passive"))
      (node (ref "R34") (pin "2") (pinfunction "2_2") (pintype "passive"))
    )
    (net (code "54") (name "Net-(Q5-B)") (class "Default")
      (node (ref "Q5") (pin "1") (pinfunction "B_1") (pintype "passive"))
      (node (ref "Q7") (pin "1") (pinfunction "B_1") (pintype "passive"))
      (node (ref "R35") (pin "1") (pinfunction "1_1") (pintype "passive"))
      (node (ref "R38") (pin "1") (pinfunction "1_1") (pintype "passive"))
    )
    (net (code "55") (name "Net-(Q5-E)") (class "Default")
      (node (ref "Q5") (pin "2") (pinfunction "E_2") (pintype "passive"))
      (node (ref "Q7") (pin "3") (pinfunction "C_3") (pintype "passive"))
      (node (ref "R34") (pin "1") (pinfunction "1_1") (pintype "passive"))
    )
    (net (code "56") (name "Net-(Q6-B)") (class "Default")
      (node (ref "Q6") (pin "1") (pinfunction "B_1") (pintype "passive"))
      (node (ref "R41") (pin "1") (pinfunction "1_1") (pintype "passive"))
      (node (ref "R42") (pin "2") (pinfunction "2_2") (pintype "passive"))
    )
    (net (code "57") (name "Net-(Q6-C)") (class "Default")
      (node (ref "Q6") (pin "3") (pinfunction "C_3") (pintype "passive"))
      (node (ref "R38") (pin "2") (pinfunction "2_2") (pintype "passive"))
    )
    (net (code "58") (name "Net-(R27-Pad1)") (class "Default")
      (node (ref "R27") (pin "1") (pinfunction "1_1") (pintype "passive"))
      (node (ref "R30") (pin "1") (pinfunction "1_1") (pintype "passive"))
      (node (ref "R36") (pin "2") (pinfunction "2_2") (pintype "passive"))
    )
    (net (code "59") (name "Net-(U3A-INA-)") (class "Default")
      (node (ref "R22") (pin "1") (pinfunction "1_1") (pintype "passive"))
      (node (ref "R29") (pin "2") (pinfunction "2_2") (pintype "passive"))
      (node (ref "U3") (pin "2") (pinfunction "INA-_2") (pintype "input"))
    )
    (net (code "60") (name "Net-(U3A-OUTA)") (class "Default")
      (node (ref "R22") (pin "2") (pinfunction "2_2") (pintype "passive"))
      (node (ref "R40") (pin "2") (pinfunction "2_2") (pintype "passive"))
      (node (ref "U3") (pin "1") (pinfunction "OUTA_1") (pintype "output"))
    )
    (net (code "61") (name "Net-(U3B-INB-)") (class "Default")
      (node (ref "C13") (pin "2") (pinfunction "2_2") (pintype "passive"))
      (node (ref "R26") (pin "1") (pinfunction "1_1") (pintype "passive"))
      (node (ref "R30") (pin "2") (pinfunction "2_2") (pintype "passive"))
      (node (ref "U3") (pin "6") (pinfunction "INB-_6") (pintype "input"))
    )
    (net (code "62") (name "Net-(U3B-OUTB)") (class "Default")
      (node (ref "C13") (pin "1") (pinfunction "1_1") (pintype "passive"))
      (node (ref "R26") (pin "2") (pinfunction "2_2") (pintype "passive"))
      (node (ref "R39") (pin "1") (pinfunction "1_1") (pintype "passive"))
      (node (ref "U3") (pin "7") (pinfunction "OUTB_7") (pintype "output"))
    )
    (net (code "63") (name "unconnected-(D1-NC-Pad3)") (class "Default")
      (node (ref "D1") (pin "3") (pinfunction "NC_3") (pintype "passive"))
    )
    (net (code "64") (name "unconnected-(U1-PB7_(XTAL2{slash}TOSC2)-Pad8)") (class "Default")
      (node (ref "U1") (pin "8") (pinfunction "PB7_(XTAL2/TOSC2)_8") (pintype "bidirectional"))
    )
    (net (code "65") (name "unconnected-(U1-PC0_(ADC0)-Pad23)") (class "Default")
      (node (ref "U1") (pin "23") (pinfunction "PC0_(ADC0)_23") (pintype "bidirectional"))
    )
    (net (code "66") (name "unconnected-(U3A-GND-Pad4)") (class "Default")
      (node (ref "U3") (pin "4") (pinfunction "GND_4") (pintype "power_in"))
    )
    (net (code "67") (name "unconnected-(U3A-V+-Pad8)") (class "Default")
      (node (ref "U3") (pin "8") (pinfunction "V+_8") (pintype "power_in"))
    )
  )
)
